# DizCharger_atmega_ardunio_sheild.net
KiCad netlist of a schematic drawn in Altium Designer
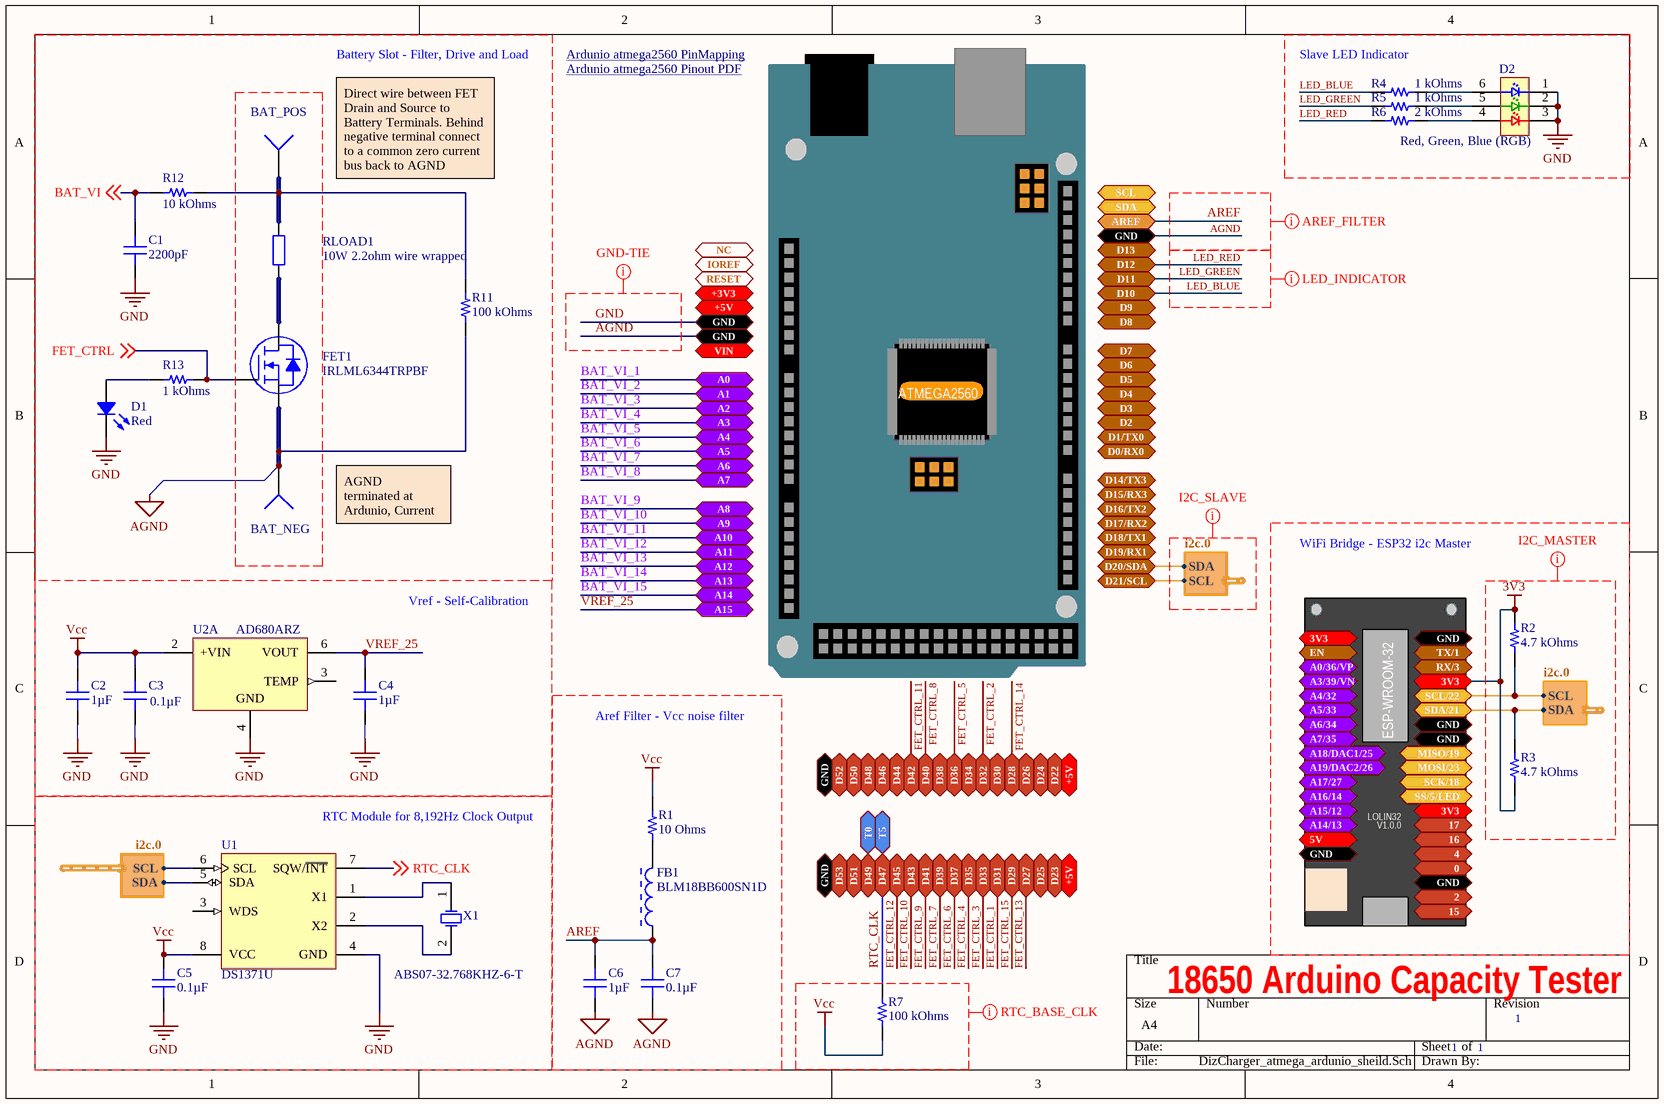
[diagram p0: DizCharger_atmega_ardunio_sheild.SchDoc]

(export (version "E")
  (design (tool "Eeschema 10.0.6"))
  (components
    (comp (ref "BAT_NEG")
      (value "Socket")
      (footprint "PIN1")
      (fields (field (name "PUBLISHER") "Altium Limited"))
      (libsource (lib "Miscellaneous Connectors") (part "Socket"))
    )
    (comp (ref "BAT_POS")
      (value "Socket")
      (footprint "PIN1")
      (fields (field (name "PUBLISHER") "Altium Limited"))
      (libsource (lib "Miscellaneous Connectors") (part "Socket"))
    )
    (comp (ref "C1")
      (value "2200pF")
      (footprint "CAP 0805_2012")
      (description "CAP CER 0805 2.2NF 250V C0G")
      (fields (field (name "PART NUMBER") "C0805C222KAGECAUTO") (field (name "MANUFACTURER") "KEMET"))
      (libsource (lib "Celestial Altium Library - altium_library") (part "Capacitor"))
    )
    (comp (ref "C2")
      (value "1µF")
      (footprint "CAP 0805_2012")
      (description "CAP CER 1UF 16V X7R 0805")
      (fields (field (name "PART NUMBER") "0805YC105KAZ2A") (field (name "MANUFACTURER") "AVX Corporation"))
      (libsource (lib "Celestial Altium Library - altium_library") (part "Capacitor"))
    )
    (comp (ref "C3")
      (value "0.1µF")
      (footprint "CAP 0805_2012")
      (description "CAP CER 0.1UF 16V X7R 0805")
      (fields
        (field (name "PART NUMBER") "0805B104K160CT")
        (field (name "MANUFACTURER") "Walsin Technology Corporation")
      )
      (libsource (lib "Celestial Altium Library - altium_library") (part "Capacitor"))
    )
    (comp (ref "C4")
      (value "1µF")
      (footprint "CAP 0805_2012")
      (description "CAP CER 1UF 16V X7R 0805")
      (fields (field (name "PART NUMBER") "0805YC105KAZ2A") (field (name "MANUFACTURER") "AVX Corporation"))
      (libsource (lib "Celestial Altium Library - altium_library") (part "Capacitor"))
    )
    (comp (ref "C5")
      (value "0.1µF")
      (footprint "CAP 0805_2012")
      (description "CAP CER 0.1UF 16V X7R 0805")
      (fields
        (field (name "PART NUMBER") "0805B104K160CT")
        (field (name "MANUFACTURER") "Walsin Technology Corporation")
      )
      (libsource (lib "Celestial Altium Library - altium_library") (part "Capacitor"))
    )
    (comp (ref "C6")
      (value "1µF")
      (footprint "CAP 0805_2012")
      (description "CAP CER 1UF 16V X7R 0805")
      (fields (field (name "PART NUMBER") "0805YC105KAZ2A") (field (name "MANUFACTURER") "AVX Corporation"))
      (libsource (lib "Celestial Altium Library - altium_library") (part "Capacitor"))
    )
    (comp (ref "C7")
      (value "0.1µF")
      (footprint "CAP 0805_2012")
      (description "CAP CER 0.1UF 16V X7R 0805")
      (fields
        (field (name "PART NUMBER") "0805B104K160CT")
        (field (name "MANUFACTURER") "Walsin Technology Corporation")
      )
      (libsource (lib "Celestial Altium Library - altium_library") (part "Capacitor"))
    )
    (comp (ref "D1")
      (value "Red")
      (footprint "LED 1206_3216 RED")
      (description "LED SMD")
      (fields (field (name "PART NUMBER") "APTL3216SURCK-01") (field (name "MANUFACTURER") "Kingbright"))
      (libsource (lib "Celestial Altium Library - altium_library") (part "LED"))
    )
    (comp (ref "D2")
      (value "Red, Green, Blue (RGB)")
      (footprint "LED PLCC6-CREE 5.5X5.3MM")
      (description "LED RGB 6PLCC SMD")
      (fields
        (field (name "PART NUMBER") "SLV6A-FKB-CK1P1G1BB7R3R3")
        (field (name "MANUFACTURER") "Cree Inc.")
      )
      (libsource (lib "Celestial Altium Library - altium_library") (part "RGB LED SLV6A"))
    )
    (comp (ref "FB1")
      (value "BLM18BB600SN1D")
      (footprint "MURA-BLM18-F-H1-CHIP-2_V")
      (fields (field (name "MANUFACTURER") "Murata"))
      (libsource (lib "Altium Content Vault") (part "MURA-FB-2"))
    )
    (comp (ref "FET1")
      (value "IRLML6344TRPBF")
      (footprint "INFINEON SOT-23-3")
      (description "MOSFET N-CH 30V 5A SOT23")
      (fields (field (name "MANUFACTURER") "Infineon Technologies"))
      (libsource (lib "Celestial Altium Library - altium_library") (part "INFINEON MOSFET N-CH SOT-23-3 GSD"))
    )
    (comp (ref "R1")
      (value "10 Ohms")
      (footprint "RES 0805_2012")
      (description "RES SMD 10 OHM 0.25% 1/5W 0805")
      (fields
        (field (name "PART NUMBER") "Y407210R0000C9W")
        (field (name "MANUFACTURER") "Vishay Foil Resistors (Division of Vishay Precision Group)")
      )
      (libsource (lib "Celestial Altium Library - altium_library") (part "Resistor"))
    )
    (comp (ref "R2")
      (value "4.7 kOhms")
      (footprint "RES 0805_2012")
      (description "RES SMD 4.7K OHM 1% 0.4W 0805")
      (fields (field (name "PART NUMBER") "RCS08054K70FKEA") (field (name "MANUFACTURER") "Vishay Dale"))
      (libsource (lib "Celestial Altium Library - altium_library") (part "Resistor"))
    )
    (comp (ref "R3")
      (value "4.7 kOhms")
      (footprint "RES 0805_2012")
      (description "RES SMD 4.7K OHM 1% 0.4W 0805")
      (fields (field (name "PART NUMBER") "RCS08054K70FKEA") (field (name "MANUFACTURER") "Vishay Dale"))
      (libsource (lib "Celestial Altium Library - altium_library") (part "Resistor"))
    )
    (comp (ref "R4")
      (value "1 kOhms")
      (footprint "RES 0805_2012")
      (description "RES 1K OHM 1% 1/5W 0805")
      (fields (field (name "PART NUMBER") "TNPW08051K00FEEA") (field (name "MANUFACTURER") "Vishay Dale"))
      (libsource (lib "Celestial Altium Library - altium_library") (part "Resistor"))
    )
    (comp (ref "R5")
      (value "1 kOhms")
      (footprint "RES 0805_2012")
      (description "RES 1K OHM 1% 1/5W 0805")
      (fields (field (name "PART NUMBER") "TNPW08051K00FEEA") (field (name "MANUFACTURER") "Vishay Dale"))
      (libsource (lib "Celestial Altium Library - altium_library") (part "Resistor"))
    )
    (comp (ref "R6")
      (value "2 kOhms")
      (footprint "RES 0805_2012")
      (description "RESA-AS 0805 2K 1% 125MW TC100")
      (fields (field (name "PART NUMBER") "CR0805AFX-2001EAS") (field (name "MANUFACTURER") "Bourns Inc."))
      (libsource (lib "Celestial Altium Library - altium_library") (part "Resistor"))
    )
    (comp (ref "R7")
      (value "100 kOhms")
      (footprint "RES 0805_2012")
      (description "RES 100K OHM 1% 1/5W 0805")
      (fields (field (name "PART NUMBER") "TNPW0805100KFEEA") (field (name "MANUFACTURER") "Vishay Dale"))
      (libsource (lib "Celestial Altium Library - altium_library") (part "Resistor"))
    )
    (comp (ref "R11")
      (value "100 kOhms")
      (footprint "RES 0805_2012")
      (description "RES 100K OHM 1% 1/5W 0805")
      (fields (field (name "PART NUMBER") "TNPW0805100KFEEA") (field (name "MANUFACTURER") "Vishay Dale"))
      (libsource (lib "Celestial Altium Library - altium_library") (part "Resistor"))
    )
    (comp (ref "R12")
      (value "10 kOhms")
      (footprint "RES 0805_2012")
      (description "RES SMD 10K OHM 1% 1/10W 0805")
      (fields
        (field (name "PART NUMBER") "Y162910K0000F9R")
        (field (name "MANUFACTURER") "Vishay Foil Resistors (Division of Vishay Precision Group)")
      )
      (libsource (lib "Celestial Altium Library - altium_library") (part "Resistor"))
    )
    (comp (ref "R13")
      (value "1 kOhms")
      (footprint "RES 0805_2012")
      (description "RES 1K OHM 1% 1/5W 0805")
      (fields (field (name "PART NUMBER") "TNPW08051K00FEEA") (field (name "MANUFACTURER") "Vishay Dale"))
      (libsource (lib "Celestial Altium Library - altium_library") (part "Resistor"))
    )
    (comp (ref "RLOAD1")
      (value "10W 2.2ohm wire wrapped")
      (footprint "AXIAL-0.4")
      (description "Resistor")
      (fields (field (name "PUBLISHER") "Altium Limited"))
      (libsource (lib "Miscellaneous Devices") (part "Res2"))
    )
    (comp (ref "U1")
      (value "DS1371U")
      (footprint "U8-1_L")
      (description "I2C, 32-bit Binary Counter Watchdog Real-Time Clock, 8-Pin uSOP, -40 to 85 degC")
      (libsource (lib "Altium Content Vault") (part "MAX-RTC-8-DS1371U-U8-1"))
    )
    (comp (ref "U2")
      (value "AD680ARZ")
      (footprint "ADI-R-8_L")
      (fields (field (name "MANUFACTURER") "Analog Devices"))
      (libsource (lib "Altium Content Vault") (part "ADI-AD680-X-8"))
    )
    (comp (ref "X1")
      (value "ABS07-32.768KHZ-6-T")
      (footprint "ABRA-ABS07_V")
      (description "Low Profile Crystal, 32.768 KHz, 6 pF, -40 to 85 degC, 2-Pin SMD, RoHS, Tape and Reel")
      (fields (field (name "TOLERANCE") "20PPM") (field (name "MANUFACTURER") "ABRACON"))
      (libsource (lib "Altium Content Vault") (part "XTAL_1-2-2"))
    )
  )
  (nets
    (net (code "23") (name "/AREF") (class "Default")
      (node (ref "C6") (pin "2") (pinfunction "2_2") (pintype "passive"))
      (node (ref "C7") (pin "2") (pinfunction "2_2") (pintype "passive"))
      (node (ref "FB1") (pin "1") (pinfunction "1_1") (pintype "passive"))
    )
    (net (code "91") (name "/LED_BLUE") (class "Default")
      (node (ref "R4") (pin "2") (pinfunction "2_2") (pintype "passive"))
    )
    (net (code "92") (name "/LED_GREEN") (class "Default")
      (node (ref "R5") (pin "2") (pinfunction "2_2") (pintype "passive"))
    )
    (net (code "93") (name "/LED_RED") (class "Default")
      (node (ref "R6") (pin "1") (pinfunction "1_1") (pintype "passive"))
    )
    (net (code "101") (name "/SCL{slash}22") (class "Default")
      (node (ref "R2") (pin "1") (pinfunction "1_1") (pintype "passive"))
    )
    (net (code "103") (name "/SDA{slash}21") (class "Default")
      (node (ref "R3") (pin "2") (pinfunction "2_2") (pintype "passive"))
    )
    (net (code "109") (name "/VREF_25") (class "Default")
      (node (ref "C4") (pin "2") (pinfunction "2_2") (pintype "passive"))
      (node (ref "U2") (pin "6") (pinfunction "VOUT_6") (pintype "power_in"))
    )
    (net (code "111") (name "3V3") (class "Default")
      (node (ref "R2") (pin "2") (pinfunction "2_2") (pintype "passive"))
      (node (ref "R3") (pin "1") (pinfunction "1_1") (pintype "passive"))
    )
    (net (code "112") (name "AGND") (class "Default")
      (node (ref "BAT_NEG") (pin "1") (pinfunction "1_1") (pintype "passive"))
      (node (ref "C1") (pin "1") (pinfunction "1_1") (pintype "passive"))
      (node (ref "C2") (pin "1") (pinfunction "1_1") (pintype "passive"))
      (node (ref "C3") (pin "1") (pinfunction "1_1") (pintype "passive"))
      (node (ref "C4") (pin "1") (pinfunction "1_1") (pintype "passive"))
      (node (ref "C5") (pin "1") (pinfunction "1_1") (pintype "passive"))
      (node (ref "C6") (pin "1") (pinfunction "1_1") (pintype "passive"))
      (node (ref "C7") (pin "1") (pinfunction "1_1") (pintype "passive"))
      (node (ref "D1") (pin "2") (pinfunction "2_2") (pintype "passive"))
      (node (ref "D2") (pin "1") (pinfunction "C1_1") (pintype "passive"))
      (node (ref "D2") (pin "2") (pinfunction "C2_2") (pintype "passive"))
      (node (ref "D2") (pin "3") (pinfunction "C3_3") (pintype "passive"))
      (node (ref "FET1") (pin "2") (pinfunction "S_2") (pintype "passive"))
      (node (ref "R11") (pin "1") (pinfunction "1_1") (pintype "passive"))
      (node (ref "U1") (pin "4") (pinfunction "GND_4") (pintype "power_in"))
      (node (ref "U2") (pin "4") (pinfunction "GND_4") (pintype "power_in"))
    )
    (net (code "113") (name "BAT_VI") (class "Default")
      (node (ref "C1") (pin "2") (pinfunction "2_2") (pintype "passive"))
      (node (ref "R12") (pin "2") (pinfunction "2_2") (pintype "passive"))
    )
    (net (code "114") (name "FET_CTRL") (class "Default")
      (node (ref "FET1") (pin "1") (pinfunction "G_1") (pintype "passive"))
      (node (ref "R13") (pin "1") (pinfunction "1_1") (pintype "passive"))
    )
    (net (code "115") (name "Net-(BAT_POS-Pad1)") (class "Default")
      (node (ref "BAT_POS") (pin "1") (pinfunction "1_1") (pintype "passive"))
      (node (ref "R11") (pin "2") (pinfunction "2_2") (pintype "passive"))
      (node (ref "R12") (pin "1") (pinfunction "1_1") (pintype "passive"))
      (node (ref "RLOAD1") (pin "2") (pinfunction "2_2") (pintype "passive"))
    )
    (net (code "116") (name "Net-(D1-Pad1)") (class "Default")
      (node (ref "D1") (pin "1") (pinfunction "1_1") (pintype "passive"))
      (node (ref "R13") (pin "2") (pinfunction "2_2") (pintype "passive"))
    )
    (net (code "117") (name "Net-(D2-A1)") (class "Default")
      (node (ref "D2") (pin "6") (pinfunction "A1_6") (pintype "passive"))
      (node (ref "R4") (pin "1") (pinfunction "1_1") (pintype "passive"))
    )
    (net (code "118") (name "Net-(D2-A2)") (class "Default")
      (node (ref "D2") (pin "5") (pinfunction "A2_5") (pintype "passive"))
      (node (ref "R5") (pin "1") (pinfunction "1_1") (pintype "passive"))
    )
    (net (code "119") (name "Net-(D2-A3)") (class "Default")
      (node (ref "D2") (pin "4") (pinfunction "A3_4") (pintype "passive"))
      (node (ref "R6") (pin "2") (pinfunction "2_2") (pintype "passive"))
    )
    (net (code "120") (name "Net-(FB1-Pad2)") (class "Default")
      (node (ref "FB1") (pin "2") (pinfunction "2_2") (pintype "passive"))
      (node (ref "R1") (pin "1") (pinfunction "1_1") (pintype "passive"))
    )
    (net (code "121") (name "Net-(FET1-D)") (class "Default")
      (node (ref "FET1") (pin "3") (pinfunction "D_3") (pintype "passive"))
      (node (ref "RLOAD1") (pin "1") (pinfunction "1_1") (pintype "passive"))
    )
    (net (code "122") (name "Net-(U1-X1)") (class "Default")
      (node (ref "U1") (pin "1") (pinfunction "X1_1") (pintype "passive"))
      (node (ref "X1") (pin "1") (pinfunction "X1_1") (pintype "passive"))
    )
    (net (code "123") (name "Net-(U1-X2)") (class "Default")
      (node (ref "U1") (pin "2") (pinfunction "X2_2") (pintype "passive"))
      (node (ref "X1") (pin "2") (pinfunction "X2_2") (pintype "passive"))
    )
    (net (code "124") (name "RTC_CLK") (class "Default")
      (node (ref "R7") (pin "2") (pinfunction "2_2") (pintype "passive"))
      (node (ref "U1") (pin "7") (pinfunction "SQW/~{INT}_7") (pintype "open_collector"))
    )
    (net (code "125") (name "Vcc") (class "Default")
      (node (ref "C2") (pin "2") (pinfunction "2_2") (pintype "passive"))
      (node (ref "C3") (pin "2") (pinfunction "2_2") (pintype "passive"))
      (node (ref "C5") (pin "2") (pinfunction "2_2") (pintype "passive"))
      (node (ref "R1") (pin "2") (pinfunction "2_2") (pintype "passive"))
      (node (ref "R7") (pin "1") (pinfunction "1_1") (pintype "passive"))
      (node (ref "U1") (pin "8") (pinfunction "VCC_8") (pintype "power_in"))
      (node (ref "U2") (pin "2") (pinfunction "+VIN_2") (pintype "power_in"))
    )
    (net (code "126") (name "unconnected-(U1-SCL-Pad6)") (class "Default")
      (node (ref "U1") (pin "6") (pinfunction "SCL_6") (pintype "input"))
    )
    (net (code "127") (name "unconnected-(U1-SDA-Pad5)") (class "Default")
      (node (ref "U1") (pin "5") (pinfunction "SDA_5") (pintype "bidirectional"))
    )
    (net (code "128") (name "unconnected-(U1-WDS-Pad3)") (class "Default")
      (node (ref "U1") (pin "3") (pinfunction "WDS_3") (pintype "input"))
    )
    (net (code "129") (name "unconnected-(U2A-TEMP-Pad3)") (class "Default")
      (node (ref "U2") (pin "3") (pinfunction "TEMP_3") (pintype "output"))
    )
  )
)
